# Distance_V1_0.net
KiCad netlist of a schematic drawn in EAGLE
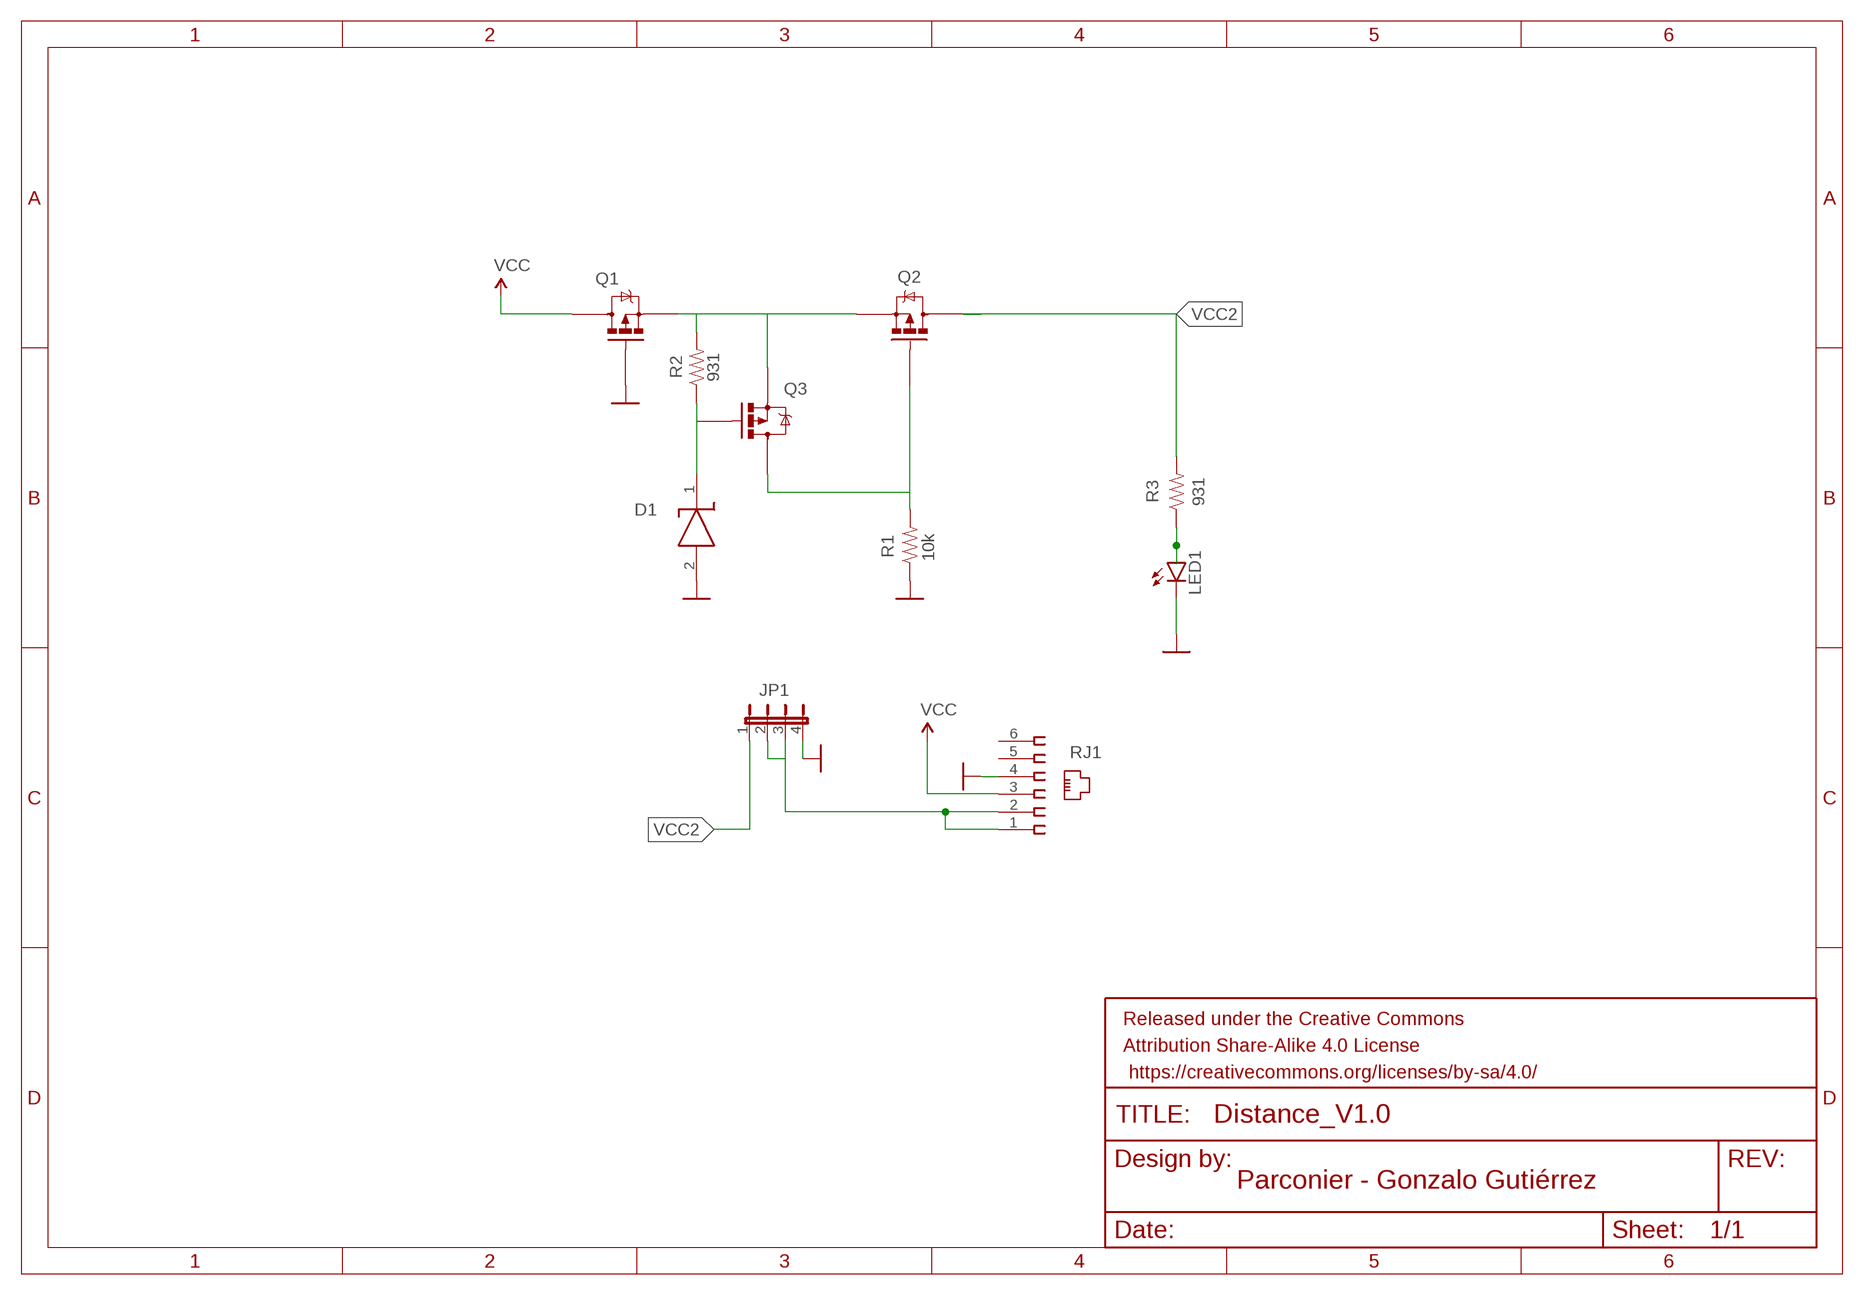
[diagram p0: schematic, sheet 1]

(export (version "E")
  (design (tool "Eeschema 10.0.6"))
  (components
    (comp (ref "D1")
      (value "BZT52C5V1-7-F")
      (footprint "eagle-import:SOD3716X145N")
      (fields (field (name "RS_PART_NUMBER") "7384951P"))
      (libsource (lib "eagle-import") (part "BZT52C5V1-7-F"))
    )
    (comp (ref "JP1")
      (value "JP4E")
      (footprint "eagle-import:JP4")
      (fields (field (name "MPN") "HC-SR04"))
      (libsource (lib "eagle-import") (part "JP4E"))
    )
    (comp (ref "LED1")
      (value "LED0603")
      (footprint "eagle-import:LED-0603")
      (fields (field (name "MPN") "LTST-C193KRKT-5A "))
      (libsource (lib "eagle-import") (part "LED0603"))
    )
    (comp (ref "Q1")
      (value "RU1C002ZPTCL")
      (footprint "eagle-import:SOTFL65P210X105-3N")
      (libsource (lib "eagle-import") (part "RU1C002ZPTCL"))
    )
    (comp (ref "Q2")
      (value "RU1C002ZPTCL")
      (footprint "eagle-import:SOTFL65P210X105-3N")
      (description "ROHM - RU1C002ZPTCL - MOSFET, P-CH, -20V, -0.2A, SOT-323FL")
      (fields
        (field (name "ARROW_PART_NUMBER") "RU1C002ZPTCL")
        (field (name "HEIGHT") "1.05mm")
        (field (name "MANUFACTURER_NAME") "ROHM Semiconductor")
        (field (name "MANUFACTURER_PART_NUMBER") "RU1C002ZPTCL")
      )
      (libsource (lib "eagle-import") (part "RU1C002ZPTCL"))
    )
    (comp (ref "Q3")
      (value "RU1C002ZPTCL")
      (footprint "eagle-import:SOTFL65P210X105-3N")
      (description "ROHM - RU1C002ZPTCL - MOSFET, P-CH, -20V, -0.2A, SOT-323FL")
      (fields
        (field (name "ARROW_PART_NUMBER") "RU1C002ZPTCL")
        (field (name "HEIGHT") "1.05mm")
        (field (name "MANUFACTURER_NAME") "ROHM Semiconductor")
        (field (name "MANUFACTURER_PART_NUMBER") "RU1C002ZPTCL")
      )
      (libsource (lib "eagle-import") (part "RU1C002ZPTCL"))
    )
    (comp (ref "R1")
      (value "10k")
      (footprint "eagle-import:RESC1005X35")
      (fields (field (name "MPN") "RC0402JR-7W10KL"))
      (libsource (lib "eagle-import") (part "RES_0402"))
    )
    (comp (ref "R2")
      (value "931")
      (footprint "eagle-import:RESC1005X35")
      (fields (field (name "MPN") "RC0402FR-07931RL"))
      (libsource (lib "eagle-import") (part "RES_0402"))
    )
    (comp (ref "R3")
      (value "931")
      (footprint "eagle-import:RESC1005X35")
      (fields (field (name "MPN") "RC0402FR-07931RL"))
      (libsource (lib "eagle-import") (part "RES_0402"))
    )
    (comp (ref "RJ1")
      (value "615006138421")
      (footprint "eagle-import:615006138421")
      (fields (field (name "RS_PART_NUMBER") "7350282") (field (name "MPN") "54601-906WPLF"))
      (libsource (lib "eagle-import") (part "615006138421"))
    )
  )
  (nets
    (net (code "1") (name "GND") (class "Default")
      (node (ref "D1") (pin "2") (pinfunction "A_2") (pintype "bidirectional"))
      (node (ref "JP1") (pin "4") (pinfunction "4_4") (pintype "passive"))
      (node (ref "LED1") (pin "C") (pinfunction "C_C") (pintype "passive"))
      (node (ref "Q1") (pin "1") (pinfunction "G_1") (pintype "bidirectional"))
      (node (ref "R1") (pin "1") (pinfunction "1_1") (pintype "passive"))
      (node (ref "RJ1") (pin "4") (pinfunction "4_4") (pintype "input"))
    )
    (net (code "2") (name "Net-(D1-K)") (class "Default")
      (node (ref "D1") (pin "1") (pinfunction "K_1") (pintype "bidirectional"))
      (node (ref "Q3") (pin "1") (pinfunction "G_1") (pintype "bidirectional"))
      (node (ref "R2") (pin "1") (pinfunction "1_1") (pintype "passive"))
    )
    (net (code "3") (name "Net-(JP1-Pad2)") (class "Default")
      (node (ref "JP1") (pin "2") (pinfunction "2_2") (pintype "passive"))
      (node (ref "JP1") (pin "3") (pinfunction "3_3") (pintype "passive"))
      (node (ref "RJ1") (pin "1") (pinfunction "1_1") (pintype "input"))
      (node (ref "RJ1") (pin "2") (pinfunction "2_2") (pintype "input"))
    )
    (net (code "4") (name "Net-(LED1-PadA)") (class "Default")
      (node (ref "LED1") (pin "A") (pinfunction "A_A") (pintype "passive"))
      (node (ref "R3") (pin "1") (pinfunction "1_1") (pintype "passive"))
    )
    (net (code "5") (name "Net-(Q1-S)") (class "Default")
      (node (ref "Q1") (pin "2") (pinfunction "S_2") (pintype "bidirectional"))
      (node (ref "Q2") (pin "2") (pinfunction "S_2") (pintype "bidirectional"))
      (node (ref "Q3") (pin "2") (pinfunction "S_2") (pintype "bidirectional"))
      (node (ref "R2") (pin "2") (pinfunction "2_2") (pintype "passive"))
    )
    (net (code "6") (name "Net-(Q2-G)") (class "Default")
      (node (ref "Q2") (pin "1") (pinfunction "G_1") (pintype "bidirectional"))
      (node (ref "Q3") (pin "3") (pinfunction "D_3") (pintype "bidirectional"))
      (node (ref "R1") (pin "2") (pinfunction "2_2") (pintype "passive"))
    )
    (net (code "7") (name "VCC") (class "Default")
      (node (ref "Q1") (pin "3") (pinfunction "D_3") (pintype "bidirectional"))
      (node (ref "RJ1") (pin "3") (pinfunction "3_3") (pintype "input"))
    )
    (net (code "8") (name "VCC2") (class "Default")
      (node (ref "JP1") (pin "1") (pinfunction "1_1") (pintype "passive"))
      (node (ref "Q2") (pin "3") (pinfunction "D_3") (pintype "bidirectional"))
      (node (ref "R3") (pin "2") (pinfunction "2_2") (pintype "passive"))
    )
    (net (code "9") (name "unconnected-(RJ1-Pad5)") (class "Default")
      (node (ref "RJ1") (pin "5") (pinfunction "5_5") (pintype "input"))
    )
    (net (code "10") (name "unconnected-(RJ1-Pad6)") (class "Default")
      (node (ref "RJ1") (pin "6") (pinfunction "6_6") (pintype "input"))
    )
  )
)
